# endstop.net
KiCad netlist of a schematic drawn in EAGLE
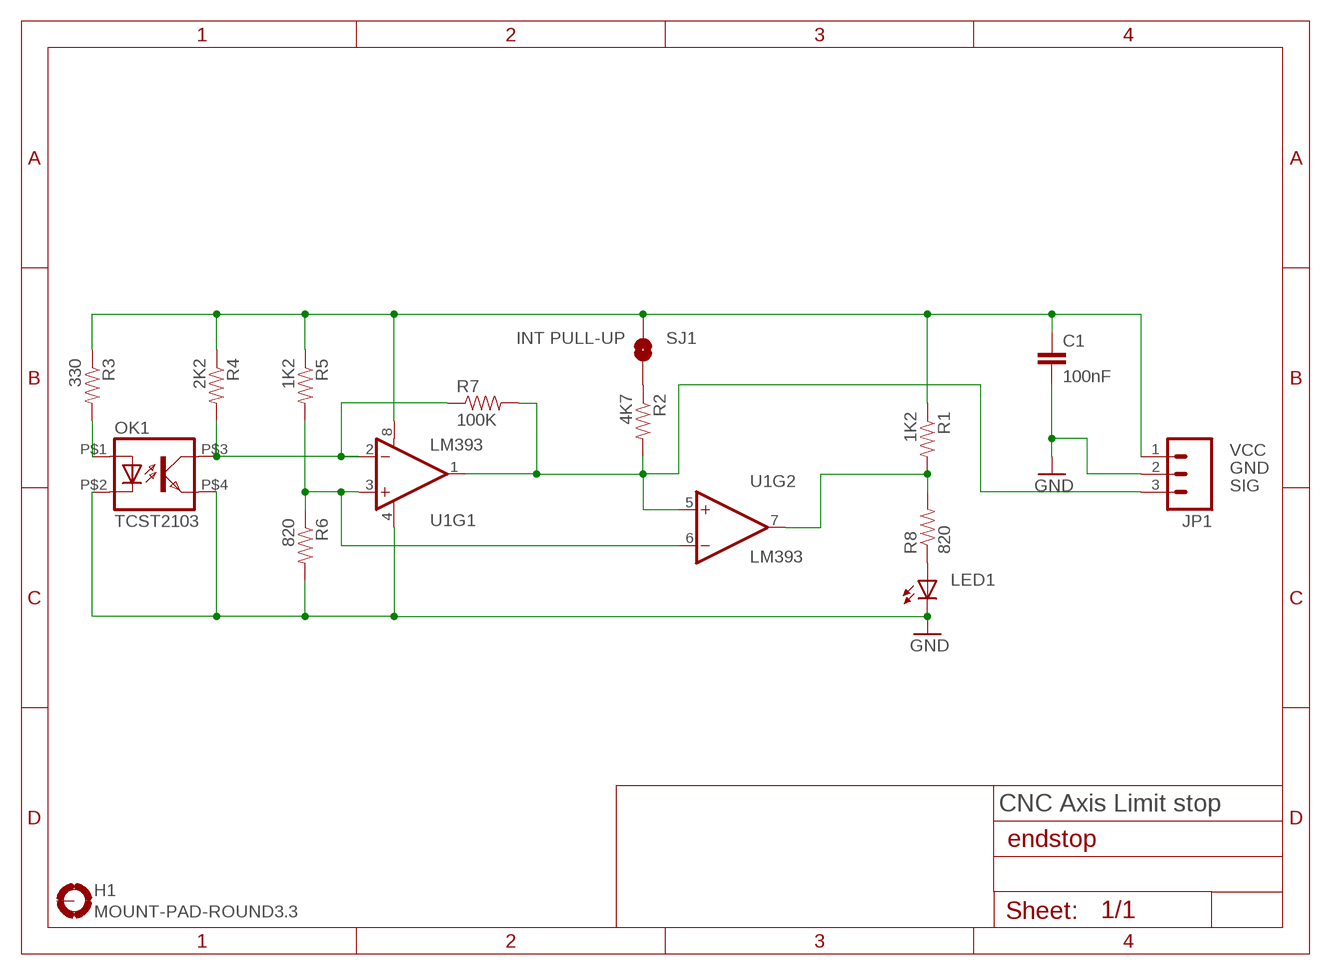
[diagram p0: schematic, sheet 1]

(export (version "E")
  (design (tool "Eeschema 10.0.6"))
  (components
    (comp (ref "C1")
      (value "100nF")
      (footprint "eagle-import:0805")
      (libsource (lib "eagle-import") (part "CAP0805"))
    )
    (comp (ref "H1")
      (value "MOUNT-PAD-ROUND3.3")
      (footprint "eagle-import:3,3-PAD")
      (libsource (lib "eagle-import") (part "MOUNT-PAD-ROUND3.3"))
    )
    (comp (ref "JP1")
      (value "M03JST-PTH")
      (footprint "eagle-import:JST-3-PTH")
      (libsource (lib "eagle-import") (part "M03JST-PTH"))
    )
    (comp (ref "LED1")
      (value "LED0603")
      (footprint "eagle-import:LED-0603")
      (libsource (lib "eagle-import") (part "LED0603"))
    )
    (comp (ref "OK1")
      (value "TCST2103")
      (footprint "eagle-import:TCST2103")
      (libsource (lib "eagle-import") (part "TCST2103"))
    )
    (comp (ref "R1")
      (value "1K2")
      (footprint "eagle-import:0805")
      (libsource (lib "eagle-import") (part "RESISTOR0805-RES"))
    )
    (comp (ref "R2")
      (value "4K7")
      (footprint "eagle-import:0805")
      (libsource (lib "eagle-import") (part "RESISTOR0805-RES"))
    )
    (comp (ref "R3")
      (value "330")
      (footprint "eagle-import:0805")
      (libsource (lib "eagle-import") (part "RESISTOR0805-RES"))
    )
    (comp (ref "R4")
      (value "2K2")
      (footprint "eagle-import:0805")
      (libsource (lib "eagle-import") (part "RESISTOR0805-RES"))
    )
    (comp (ref "R5")
      (value "1K2")
      (footprint "eagle-import:0805")
      (libsource (lib "eagle-import") (part "RESISTOR0805-RES"))
    )
    (comp (ref "R6")
      (value "820")
      (footprint "eagle-import:0805")
      (libsource (lib "eagle-import") (part "RESISTOR0805-RES"))
    )
    (comp (ref "R7")
      (value "100K")
      (footprint "eagle-import:0805")
      (libsource (lib "eagle-import") (part "RESISTOR0805-RES"))
    )
    (comp (ref "R8")
      (value "820")
      (footprint "eagle-import:0805")
      (libsource (lib "eagle-import") (part "RESISTOR0805-RES"))
    )
    (comp (ref "SJ1")
      (value "INT PULL-UP")
      (footprint "eagle-import:SJ_2S-NO")
      (libsource (lib "eagle-import") (part "SOLDERJUMPERNO"))
    )
    (comp (ref "U1")
      (value "LM393")
      (footprint "eagle-import:SO08")
      (libsource (lib "eagle-import") (part "LM393"))
    )
  )
  (nets
    (net (code "1") (name "/SIG") (class "Default")
      (node (ref "JP1") (pin "3") (pinfunction "3_3") (pintype "passive"))
      (node (ref "R2") (pin "2") (pinfunction "2_2") (pintype "passive"))
      (node (ref "R7") (pin "2") (pinfunction "2_2") (pintype "passive"))
      (node (ref "U1") (pin "1") (pinfunction "OUT_1") (pintype "output"))
      (node (ref "U1") (pin "5") (pinfunction "+IN_5") (pintype "input"))
    )
    (net (code "2") (name "/VCC") (class "Default")
      (node (ref "C1") (pin "1") (pinfunction "1_1") (pintype "passive"))
      (node (ref "JP1") (pin "1") (pinfunction "1_1") (pintype "passive"))
      (node (ref "R1") (pin "1") (pinfunction "1_1") (pintype "passive"))
      (node (ref "R3") (pin "1") (pinfunction "1_1") (pintype "passive"))
      (node (ref "R4") (pin "1") (pinfunction "1_1") (pintype "passive"))
      (node (ref "R5") (pin "1") (pinfunction "1_1") (pintype "passive"))
      (node (ref "SJ1") (pin "2") (pinfunction "2_2") (pintype "passive"))
      (node (ref "U1") (pin "8") (pinfunction "V+_8") (pintype "power_in"))
    )
    (net (code "3") (name "GND") (class "Default")
      (node (ref "C1") (pin "2") (pinfunction "2_2") (pintype "passive"))
      (node (ref "JP1") (pin "2") (pinfunction "2_2") (pintype "passive"))
      (node (ref "LED1") (pin "C") (pinfunction "C_C") (pintype "passive"))
      (node (ref "OK1") (pin "P$2") (pinfunction "C_P$2") (pintype "passive"))
      (node (ref "OK1") (pin "P$4") (pinfunction "EMIT_P$4") (pintype "passive"))
      (node (ref "R6") (pin "2") (pinfunction "2_2") (pintype "passive"))
      (node (ref "U1") (pin "4") (pinfunction "V-_4") (pintype "power_in"))
    )
    (net (code "4") (name "Net-(LED1-PadA)") (class "Default")
      (node (ref "LED1") (pin "A") (pinfunction "A_A") (pintype "passive"))
      (node (ref "R8") (pin "1") (pinfunction "1_1") (pintype "passive"))
    )
    (net (code "5") (name "Net-(OK1-A)") (class "Default")
      (node (ref "OK1") (pin "P$1") (pinfunction "A_P$1") (pintype "passive"))
      (node (ref "R3") (pin "2") (pinfunction "2_2") (pintype "passive"))
    )
    (net (code "6") (name "Net-(OK1-COL)") (class "Default")
      (node (ref "OK1") (pin "P$3") (pinfunction "COL_P$3") (pintype "passive"))
      (node (ref "R4") (pin "2") (pinfunction "2_2") (pintype "passive"))
      (node (ref "R7") (pin "1") (pinfunction "1_1") (pintype "passive"))
      (node (ref "U1") (pin "2") (pinfunction "-IN_2") (pintype "input"))
    )
    (net (code "7") (name "Net-(R2-Pad1)") (class "Default")
      (node (ref "R2") (pin "1") (pinfunction "1_1") (pintype "passive"))
      (node (ref "SJ1") (pin "1") (pinfunction "1_1") (pintype "passive"))
    )
    (net (code "8") (name "Net-(U1A-+IN)") (class "Default")
      (node (ref "R5") (pin "2") (pinfunction "2_2") (pintype "passive"))
      (node (ref "R6") (pin "1") (pinfunction "1_1") (pintype "passive"))
      (node (ref "U1") (pin "3") (pinfunction "+IN_3") (pintype "input"))
      (node (ref "U1") (pin "6") (pinfunction "-IN_6") (pintype "input"))
    )
    (net (code "9") (name "Net-(U1B-OUT)") (class "Default")
      (node (ref "R1") (pin "2") (pinfunction "2_2") (pintype "passive"))
      (node (ref "R8") (pin "2") (pinfunction "2_2") (pintype "passive"))
      (node (ref "U1") (pin "7") (pinfunction "OUT_7") (pintype "output"))
    )
    (net (code "10") (name "unconnected-(H1-MOUNT-PadB3,3)") (class "Default")
      (node (ref "H1") (pin "B3,3") (pinfunction "MOUNT_B3,3") (pintype "passive"))
    )
  )
)
